# Amplifiers.net
KiCad netlist of a schematic drawn in Altium Designer
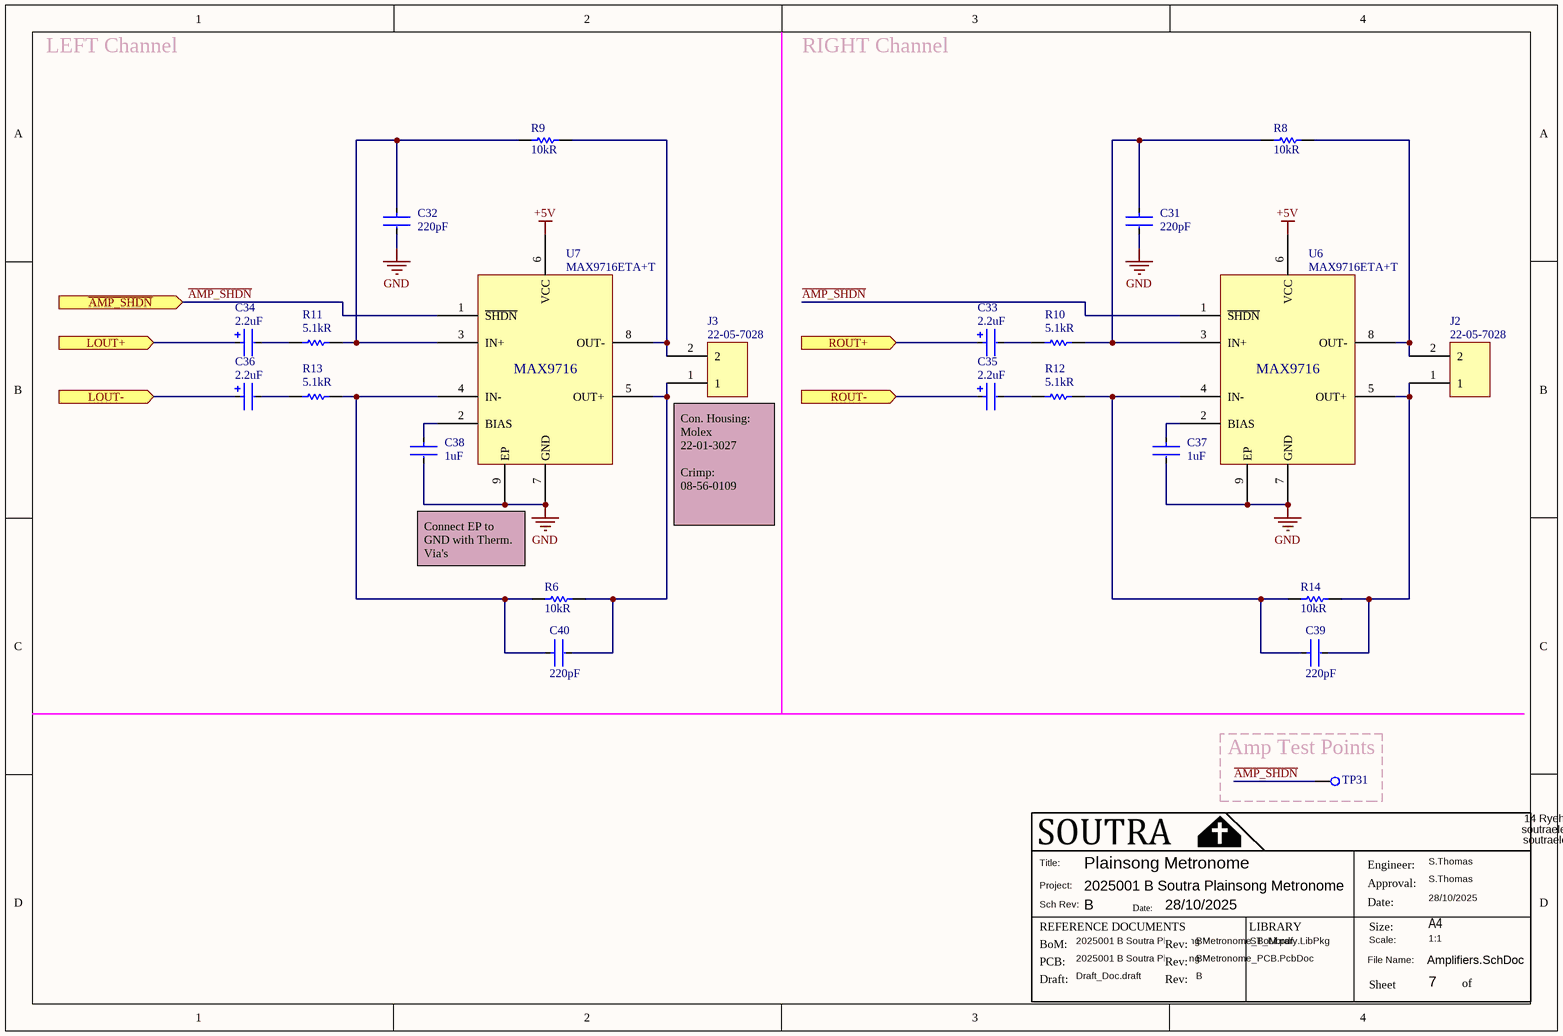
[diagram p0: Amplifiers.SchDoc]

(export (version "E")
  (design (tool "Eeschema 10.0.6"))
  (components
    (comp (ref "C31")
      (value "220pF")
      (footprint "CAPC1005X06L")
      (fields
        (field (name "MANUFACTURER") "Yageo")
        (field (name "MANUFACTURER PART NUMBER") "CC0402KPX7R9BB221")
        (field (name "ALTERNATIVE PART") "MC0402B221K500CT")
      )
      (libsource (lib "ST_Library") (part "CC0402KPX7R9BB221"))
    )
    (comp (ref "C32")
      (value "220pF")
      (footprint "CAPC1005X06L")
      (fields
        (field (name "MANUFACTURER") "Yageo")
        (field (name "MANUFACTURER PART NUMBER") "CC0402KPX7R9BB221")
        (field (name "ALTERNATIVE PART") "MC0402B221K500CT")
      )
      (libsource (lib "ST_Library") (part "CC0402KPX7R9BB221"))
    )
    (comp (ref "C33")
      (value "2.2uF")
      (footprint "CAPC2113X120X50ML20T30")
      (description "Surface Mount Tantalum Capacitor, 2.2 µF, 16 V, 0805 [2012 Metric], ± 10%, 6.5 ohm, R")
      (fields
        (field (name "MANUFACTURER") "AVX Interconnect / Elco")
        (field (name "PART NUMBER") "TAJR225K016RNJ")
      )
      (libsource (lib "ST_Library") (part "TAJR225K016RNJ"))
    )
    (comp (ref "C34")
      (value "2.2uF")
      (footprint "CAPC2113X120X50ML20T30")
      (description "Surface Mount Tantalum Capacitor, 2.2 µF, 16 V, 0805 [2012 Metric], ± 10%, 6.5 ohm, R")
      (fields
        (field (name "MANUFACTURER") "AVX Interconnect / Elco")
        (field (name "PART NUMBER") "TAJR225K016RNJ")
      )
      (libsource (lib "ST_Library") (part "TAJR225K016RNJ"))
    )
    (comp (ref "C35")
      (value "2.2uF")
      (footprint "CAPC2113X120X50ML20T30")
      (description "Surface Mount Tantalum Capacitor, 2.2 µF, 16 V, 0805 [2012 Metric], ± 10%, 6.5 ohm, R")
      (fields
        (field (name "MANUFACTURER") "AVX Interconnect / Elco")
        (field (name "PART NUMBER") "TAJR225K016RNJ")
      )
      (libsource (lib "ST_Library") (part "TAJR225K016RNJ"))
    )
    (comp (ref "C36")
      (value "2.2uF")
      (footprint "CAPC2113X120X50ML20T30")
      (description "Surface Mount Tantalum Capacitor, 2.2 µF, 16 V, 0805 [2012 Metric], ± 10%, 6.5 ohm, R")
      (fields
        (field (name "MANUFACTURER") "AVX Interconnect / Elco")
        (field (name "PART NUMBER") "TAJR225K016RNJ")
      )
      (libsource (lib "ST_Library") (part "TAJR225K016RNJ"))
    )
    (comp (ref "C37")
      (value "1uF")
      (footprint "CAPC1005X06L")
      (fields
        (field (name "MANUFACTURER") "Yageo")
        (field (name "MANUFACTURER PART NUMBER") "CC0402KRX5R6BB105")
        (field (name "ALTERNATIVE PART") "0402ZD105KAT2A")
      )
      (libsource (lib "ST_Library") (part "CC0402KRX5R6BB105"))
    )
    (comp (ref "C38")
      (value "1uF")
      (footprint "CAPC1005X06L")
      (fields
        (field (name "MANUFACTURER") "Yageo")
        (field (name "MANUFACTURER PART NUMBER") "CC0402KRX5R6BB105")
        (field (name "ALTERNATIVE PART") "0402ZD105KAT2A")
      )
      (libsource (lib "ST_Library") (part "CC0402KRX5R6BB105"))
    )
    (comp (ref "C39")
      (value "220pF")
      (footprint "CAPC1005X06L")
      (fields
        (field (name "MANUFACTURER") "Yageo")
        (field (name "MANUFACTURER PART NUMBER") "CC0402KPX7R9BB221")
        (field (name "ALTERNATIVE PART") "MC0402B221K500CT")
      )
      (libsource (lib "ST_Library") (part "CC0402KPX7R9BB221"))
    )
    (comp (ref "C40")
      (value "220pF")
      (footprint "CAPC1005X06L")
      (fields
        (field (name "MANUFACTURER") "Yageo")
        (field (name "MANUFACTURER PART NUMBER") "CC0402KPX7R9BB221")
        (field (name "ALTERNATIVE PART") "MC0402B221K500CT")
      )
      (libsource (lib "ST_Library") (part "CC0402KPX7R9BB221"))
    )
    (comp (ref "J2")
      (value "22-05-7028")
      (footprint "J_MOLEX_22-05-7028")
      (fields (field (name "MANUFACTURER") "Molex"))
      (libsource (lib "ST_Library") (part "22-05-7028"))
    )
    (comp (ref "J3")
      (value "22-05-7028")
      (footprint "J_MOLEX_22-05-7028")
      (fields (field (name "MANUFACTURER") "Molex"))
      (libsource (lib "ST_Library") (part "22-05-7028"))
    )
    (comp (ref "R6")
      (value "10kR")
      (footprint "RESC_0805_2013X50X30LL20T20")
      (fields
        (field (name "MANUFACTURER") "Yageo")
        (field (name "MANUFACTURER PART NUMBER") "RC0805JR-0710KL")
        (field (name "TOLERANCE") "5%")
      )
      (libsource (lib "ST_Library") (part "RC0805JR-0710KL"))
    )
    (comp (ref "R8")
      (value "10kR")
      (footprint "RESC_0805_2013X50X30LL20T20")
      (fields
        (field (name "MANUFACTURER") "Yageo")
        (field (name "MANUFACTURER PART NUMBER") "RC0805JR-0710KL")
        (field (name "TOLERANCE") "5%")
      )
      (libsource (lib "ST_Library") (part "RC0805JR-0710KL"))
    )
    (comp (ref "R9")
      (value "10kR")
      (footprint "RESC_0805_2013X50X30LL20T20")
      (fields
        (field (name "MANUFACTURER") "Yageo")
        (field (name "MANUFACTURER PART NUMBER") "RC0805JR-0710KL")
        (field (name "TOLERANCE") "5%")
      )
      (libsource (lib "ST_Library") (part "RC0805JR-0710KL"))
    )
    (comp (ref "R10")
      (value "5.1kR")
      (footprint "RESC_0603_1608X06L")
      (description "Fixed Resistor, 0.1W, 5100ohm, 75V, 5% +/-Tol, 100ppm/Cel, Surface Mount, 0603")
      (fields
        (field (name "MANUFACTURER") "Multicomp")
        (field (name "MANUFACTURER PART NUMBER") "MCMR06X512JTL")
      )
      (libsource (lib "ST_Library") (part "MCMR06X512JTL"))
    )
    (comp (ref "R11")
      (value "5.1kR")
      (footprint "RESC_0603_1608X06L")
      (description "Fixed Resistor, 0.1W, 5100ohm, 75V, 5% +/-Tol, 100ppm/Cel, Surface Mount, 0603")
      (fields
        (field (name "MANUFACTURER") "Multicomp")
        (field (name "MANUFACTURER PART NUMBER") "MCMR06X512JTL")
      )
      (libsource (lib "ST_Library") (part "MCMR06X512JTL"))
    )
    (comp (ref "R12")
      (value "5.1kR")
      (footprint "RESC_0603_1608X06L")
      (description "Fixed Resistor, 0.1W, 5100ohm, 75V, 5% +/-Tol, 100ppm/Cel, Surface Mount, 0603")
      (fields
        (field (name "MANUFACTURER") "Multicomp")
        (field (name "MANUFACTURER PART NUMBER") "MCMR06X512JTL")
      )
      (libsource (lib "ST_Library") (part "MCMR06X512JTL"))
    )
    (comp (ref "R13")
      (value "5.1kR")
      (footprint "RESC_0603_1608X06L")
      (description "Fixed Resistor, 0.1W, 5100ohm, 75V, 5% +/-Tol, 100ppm/Cel, Surface Mount, 0603")
      (fields
        (field (name "MANUFACTURER") "Multicomp")
        (field (name "MANUFACTURER PART NUMBER") "MCMR06X512JTL")
      )
      (libsource (lib "ST_Library") (part "MCMR06X512JTL"))
    )
    (comp (ref "R14")
      (value "10kR")
      (footprint "RESC_0805_2013X50X30LL20T20")
      (fields
        (field (name "MANUFACTURER") "Yageo")
        (field (name "MANUFACTURER PART NUMBER") "RC0805JR-0710KL")
        (field (name "TOLERANCE") "5%")
      )
      (libsource (lib "ST_Library") (part "RC0805JR-0710KL"))
    )
    (comp (ref "TP31")
      (value "TP_CIRCLE_R1")
      (footprint "TP_CIRCLE_R1")
      (description "Test Point, SMD, Circular, Radius = 1mm")
      (libsource (lib "ST_Library") (part "TP_CIRCLE_R1"))
    )
    (comp (ref "U6")
      (value "MAX9716ETA+T")
      (footprint "TDFN300X300X80_HS-9L")
      (description "Audio Amplifier, 1.4W, 1 Channel(s), 1 Func, BICMOS")
      (fields (field (name "MANUFACTURER") "Maxim"))
      (libsource (lib "ST_Library") (part "MAX9716ETA+T"))
    )
    (comp (ref "U7")
      (value "MAX9716ETA+T")
      (footprint "TDFN300X300X80_HS-9L")
      (description "Audio Amplifier, 1.4W, 1 Channel(s), 1 Func, BICMOS")
      (fields (field (name "MANUFACTURER") "Maxim"))
      (libsource (lib "ST_Library") (part "MAX9716ETA+T"))
    )
  )
  (nets
    (net (code "1") (name "+5V") (class "Default")
      (node (ref "U6") (pin "6") (pinfunction "VCC_6") (pintype "passive"))
      (node (ref "U7") (pin "6") (pinfunction "VCC_6") (pintype "passive"))
    )
    (net (code "2") (name "/LOUT+") (class "Default")
      (node (ref "C34") (pin "1") (pinfunction "1_1") (pintype "passive"))
    )
    (net (code "3") (name "/LOUT-") (class "Default")
      (node (ref "C36") (pin "1") (pinfunction "1_1") (pintype "passive"))
    )
    (net (code "4") (name "/ROUT+") (class "Default")
      (node (ref "C33") (pin "1") (pinfunction "1_1") (pintype "passive"))
    )
    (net (code "5") (name "/ROUT-") (class "Default")
      (node (ref "C35") (pin "1") (pinfunction "1_1") (pintype "passive"))
    )
    (net (code "6") (name "/~{AMP_SHDN}") (class "Default")
      (node (ref "TP31") (pin "1") (pinfunction "1_1") (pintype "passive"))
      (node (ref "U6") (pin "1") (pinfunction "~{SHDN}_1") (pintype "passive"))
      (node (ref "U7") (pin "1") (pinfunction "~{SHDN}_1") (pintype "passive"))
    )
    (net (code "7") (name "GND") (class "Default")
      (node (ref "C31") (pin "2") (pinfunction "2_2") (pintype "passive"))
      (node (ref "C32") (pin "2") (pinfunction "2_2") (pintype "passive"))
      (node (ref "C37") (pin "2") (pinfunction "2_2") (pintype "passive"))
      (node (ref "C38") (pin "2") (pinfunction "2_2") (pintype "passive"))
      (node (ref "U6") (pin "7") (pinfunction "GND_7") (pintype "passive"))
      (node (ref "U6") (pin "9") (pinfunction "EP_9") (pintype "passive"))
      (node (ref "U7") (pin "7") (pinfunction "GND_7") (pintype "passive"))
      (node (ref "U7") (pin "9") (pinfunction "EP_9") (pintype "passive"))
    )
    (net (code "8") (name "Net-(C33-Pad2)") (class "Default")
      (node (ref "C33") (pin "2") (pinfunction "2_2") (pintype "passive"))
      (node (ref "R10") (pin "1") (pinfunction "1_1") (pintype "passive"))
    )
    (net (code "9") (name "Net-(C34-Pad2)") (class "Default")
      (node (ref "C34") (pin "2") (pinfunction "2_2") (pintype "passive"))
      (node (ref "R11") (pin "1") (pinfunction "1_1") (pintype "passive"))
    )
    (net (code "10") (name "Net-(C35-Pad2)") (class "Default")
      (node (ref "C35") (pin "2") (pinfunction "2_2") (pintype "passive"))
      (node (ref "R12") (pin "1") (pinfunction "1_1") (pintype "passive"))
    )
    (net (code "11") (name "Net-(C36-Pad2)") (class "Default")
      (node (ref "C36") (pin "2") (pinfunction "2_2") (pintype "passive"))
      (node (ref "R13") (pin "1") (pinfunction "1_1") (pintype "passive"))
    )
    (net (code "12") (name "Net-(U6-BIAS)") (class "Default")
      (node (ref "C37") (pin "1") (pinfunction "1_1") (pintype "passive"))
      (node (ref "U6") (pin "2") (pinfunction "BIAS_2") (pintype "passive"))
    )
    (net (code "13") (name "Net-(U6-IN+)") (class "Default")
      (node (ref "C31") (pin "1") (pinfunction "1_1") (pintype "passive"))
      (node (ref "R10") (pin "2") (pinfunction "2_2") (pintype "passive"))
      (node (ref "R8") (pin "2") (pinfunction "2_2") (pintype "passive"))
      (node (ref "U6") (pin "3") (pinfunction "IN+_3") (pintype "passive"))
    )
    (net (code "14") (name "Net-(U6-IN-)") (class "Default")
      (node (ref "C39") (pin "1") (pinfunction "1_1") (pintype "passive"))
      (node (ref "R12") (pin "2") (pinfunction "2_2") (pintype "passive"))
      (node (ref "R14") (pin "2") (pinfunction "2_2") (pintype "passive"))
      (node (ref "U6") (pin "4") (pinfunction "IN-_4") (pintype "passive"))
    )
    (net (code "15") (name "Net-(U6-OUT+)") (class "Default")
      (node (ref "C39") (pin "2") (pinfunction "2_2") (pintype "passive"))
      (node (ref "J2") (pin "1") (pinfunction "1_1") (pintype "passive"))
      (node (ref "R14") (pin "1") (pinfunction "1_1") (pintype "passive"))
      (node (ref "U6") (pin "5") (pinfunction "OUT+_5") (pintype "passive"))
    )
    (net (code "16") (name "Net-(U6-OUT-)") (class "Default")
      (node (ref "J2") (pin "2") (pinfunction "2_2") (pintype "passive"))
      (node (ref "R8") (pin "1") (pinfunction "1_1") (pintype "passive"))
      (node (ref "U6") (pin "8") (pinfunction "OUT-_8") (pintype "passive"))
    )
    (net (code "17") (name "Net-(U7-BIAS)") (class "Default")
      (node (ref "C38") (pin "1") (pinfunction "1_1") (pintype "passive"))
      (node (ref "U7") (pin "2") (pinfunction "BIAS_2") (pintype "passive"))
    )
    (net (code "18") (name "Net-(U7-IN+)") (class "Default")
      (node (ref "C32") (pin "1") (pinfunction "1_1") (pintype "passive"))
      (node (ref "R11") (pin "2") (pinfunction "2_2") (pintype "passive"))
      (node (ref "R9") (pin "2") (pinfunction "2_2") (pintype "passive"))
      (node (ref "U7") (pin "3") (pinfunction "IN+_3") (pintype "passive"))
    )
    (net (code "19") (name "Net-(U7-IN-)") (class "Default")
      (node (ref "C40") (pin "1") (pinfunction "1_1") (pintype "passive"))
      (node (ref "R13") (pin "2") (pinfunction "2_2") (pintype "passive"))
      (node (ref "R6") (pin "2") (pinfunction "2_2") (pintype "passive"))
      (node (ref "U7") (pin "4") (pinfunction "IN-_4") (pintype "passive"))
    )
    (net (code "20") (name "Net-(U7-OUT+)") (class "Default")
      (node (ref "C40") (pin "2") (pinfunction "2_2") (pintype "passive"))
      (node (ref "J3") (pin "1") (pinfunction "1_1") (pintype "passive"))
      (node (ref "R6") (pin "1") (pinfunction "1_1") (pintype "passive"))
      (node (ref "U7") (pin "5") (pinfunction "OUT+_5") (pintype "passive"))
    )
    (net (code "21") (name "Net-(U7-OUT-)") (class "Default")
      (node (ref "J3") (pin "2") (pinfunction "2_2") (pintype "passive"))
      (node (ref "R9") (pin "1") (pinfunction "1_1") (pintype "passive"))
      (node (ref "U7") (pin "8") (pinfunction "OUT-_8") (pintype "passive"))
    )
  )
)
